# 3_waffling80_classyTKL-NMB_mcu.net
KiCad netlist of a schematic drawn in Altium Designer
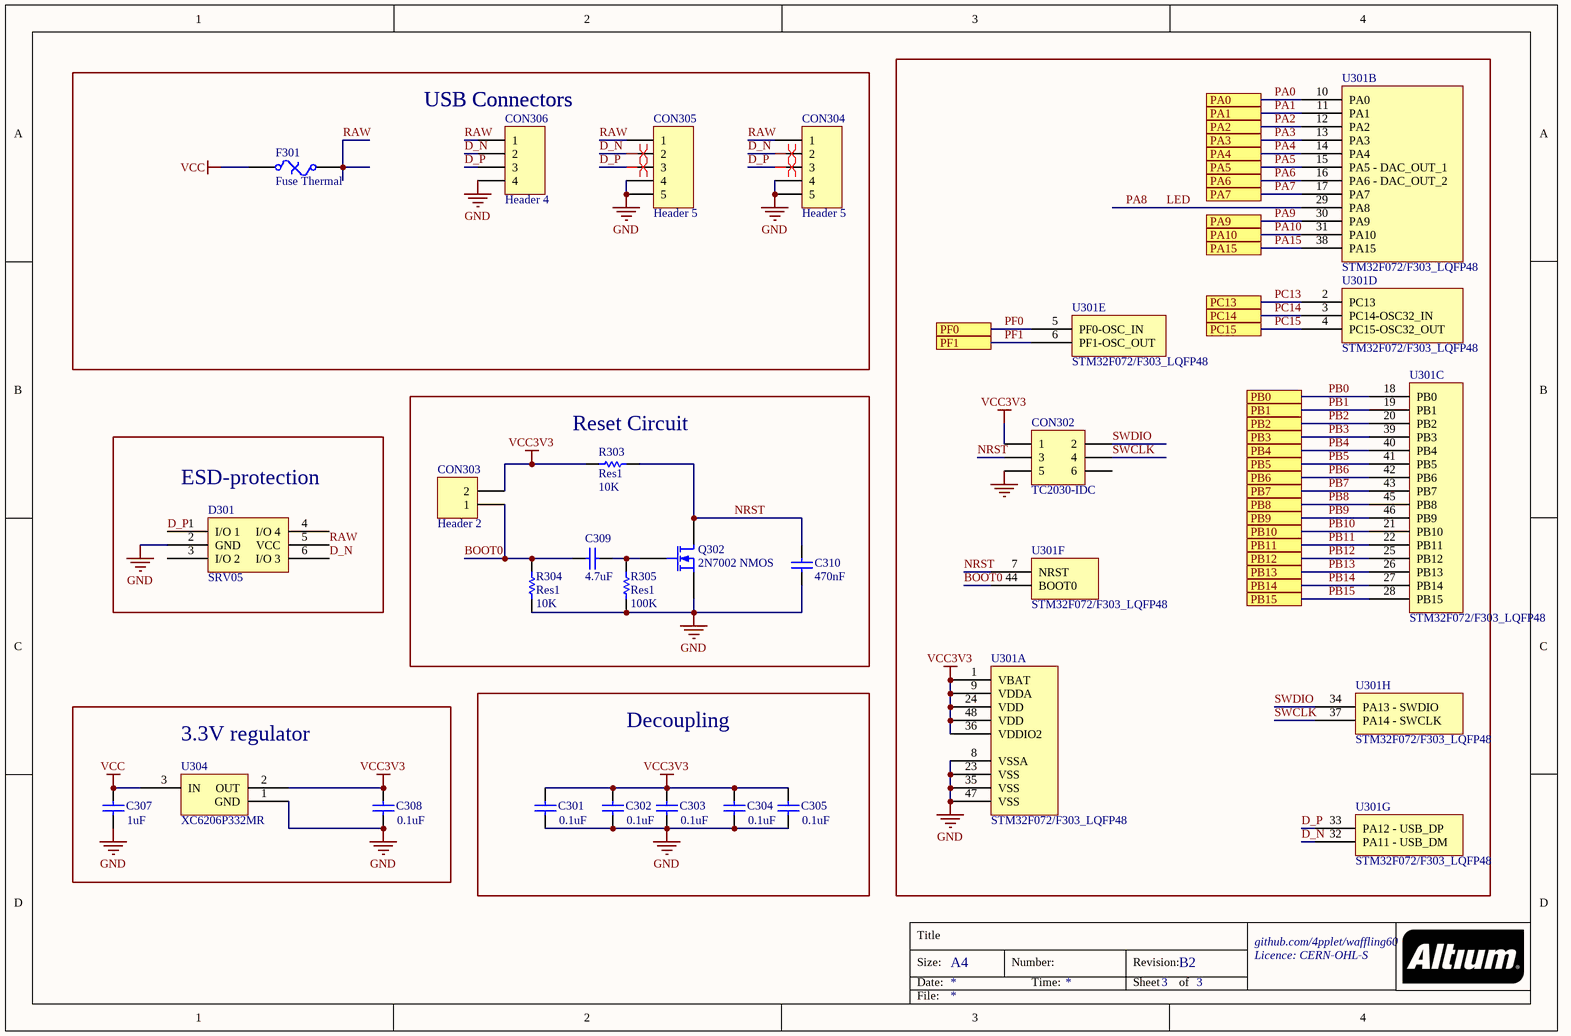
[diagram p0: 3_waffling80_classyTKL-NMB_mcu.SchDoc]

(export (version "E")
  (design (tool "Eeschema 10.0.6"))
  (components
    (comp (ref "C301")
      (value "0.1uF")
      (footprint "C0603[1608]")
      (description "Capacitor")
      (fields (field (name "LCSC PART #") "C14663") (field (name "MRF.PART") "CC0603KRX7R9BB104"))
      (libsource (lib "Miscellaneous Devices") (part "Cap"))
    )
    (comp (ref "C302")
      (value "0.1uF")
      (footprint "C0603[1608]")
      (description "Capacitor")
      (fields (field (name "LCSC PART #") "C14663") (field (name "MRF.PART") "CC0603KRX7R9BB104"))
      (libsource (lib "Miscellaneous Devices") (part "Cap"))
    )
    (comp (ref "C303")
      (value "0.1uF")
      (footprint "C0603[1608]")
      (description "Capacitor")
      (fields (field (name "LCSC PART #") "C14663") (field (name "MRF.PART") "CC0603KRX7R9BB104"))
      (libsource (lib "Miscellaneous Devices") (part "Cap"))
    )
    (comp (ref "C304")
      (value "0.1uF")
      (footprint "C0603[1608]")
      (description "Capacitor")
      (fields (field (name "LCSC PART #") "C14663") (field (name "MRF.PART") "CC0603KRX7R9BB104"))
      (libsource (lib "Miscellaneous Devices") (part "Cap"))
    )
    (comp (ref "C305")
      (value "0.1uF")
      (footprint "C0603[1608]")
      (description "Capacitor")
      (fields (field (name "LCSC PART #") "C14663") (field (name "MRF.PART") "CC0603KRX7R9BB104"))
      (libsource (lib "Miscellaneous Devices") (part "Cap"))
    )
    (comp (ref "C307")
      (value "1uF")
      (footprint "C0603[1608]")
      (description "Capacitor")
      (fields (field (name "LCSC PART #") "C15849") (field (name "MRF.PART") "CL10A105KB8NNNC"))
      (libsource (lib "Miscellaneous Devices") (part "Cap"))
    )
    (comp (ref "C308")
      (value "0.1uF")
      (footprint "C0603[1608]")
      (description "Capacitor")
      (fields (field (name "LCSC PART #") "C14663") (field (name "MRF.PART") "CC0603KRX7R9BB104"))
      (libsource (lib "Miscellaneous Devices") (part "Cap"))
    )
    (comp (ref "C309")
      (value "4.7uF")
      (footprint "C0603[1608]")
      (description "Capacitor")
      (fields (field (name "LCSC PART #") "C19666") (field (name "MRF.PART") "CL10A475KO8NNNC"))
      (libsource (lib "Miscellaneous Devices") (part "Cap"))
    )
    (comp (ref "C310")
      (value "470nF")
      (footprint "C0603[1608]")
      (description "Capacitor")
      (fields (field (name "LCSC PART #") "C1623") (field (name "MRF.PART") "CL10B474KA8NNNC"))
      (libsource (lib "Miscellaneous Devices") (part "Cap"))
    )
    (comp (ref "CON302")
      (value "TC2030-IDC")
      (footprint "TC2030-IDC-NL")
      (description "Header, 3-Pin, Dual row")
      (libsource (lib "Miscellaneous Connectors") (part "Header 3X2"))
    )
    (comp (ref "CON303")
      (value "Header 2")
      (footprint "HDR1X2")
      (description "Header, 2-Pin")
      (libsource (lib "Miscellaneous Connectors") (part "Header 2"))
    )
    (comp (ref "CON304")
      (value "Header 5")
      (footprint "UDB_COMBO_JST_MOLEX")
      (description "JST for USB daughter board")
      (fields (field (name "LCSC PART #") "C160404") (field (name "MRF.PART") "SM04B-SRSS-TB(LF)(SN)"))
      (libsource (lib "Miscellaneous Connectors") (part "Header 5"))
    )
    (comp (ref "CON305")
      (value "Header 5")
      (footprint "Molex 781710004")
      (description "JST for USB daughter board")
      (fields (field (name "LCSC PART #") "C588524") (field (name "MRF.PART") "781710004"))
      (libsource (lib "Miscellaneous Connectors") (part "Header 5"))
    )
    (comp (ref "CON306")
      (value "Header 4")
      (footprint "HDR1X4")
      (description "Header, 4-Pin")
      (libsource (lib "Miscellaneous Connectors") (part "Header 4"))
    )
    (comp (ref "D301")
      (value "SRV05")
      (footprint "SOT-23-6")
      (fields (field (name "LCSC PART #") "C85364") (field (name "MRF.PART") "SRV05-4-P-T7"))
      (libsource (lib "Keebs") (part "SRV05"))
    )
    (comp (ref "F301")
      (value "Fuse Thermal")
      (footprint "C1206[3216]")
      (description "Thermal Fuse")
      (fields (field (name "LCSC PART #") "C135338") (field (name "MRF.PART") "ASMD1206-050"))
      (libsource (lib "Miscellaneous Devices") (part "Fuse Thermal"))
    )
    (comp (ref "Q302")
      (value "2N7002 NMOS")
      (footprint "SOT-23-3")
      (description "N-Channel MOSFET")
      (fields (field (name "LCSC PART #") "C8545") (field (name "MRF.PART") "2N7002"))
      (libsource (lib "Miscellaneous Devices") (part "MOSFET-N"))
    )
    (comp (ref "R303")
      (value "Res1")
      (footprint "R0603[1608]")
      (description "Resistor")
      (fields
        (field (name "ALTIUM_VALUE") "10K")
        (field (name "LCSC PART #") "C25804")
        (field (name "MRF.PART") "0603WAF1002T5E")
      )
      (libsource (lib "Miscellaneous Devices") (part "Res1"))
    )
    (comp (ref "R304")
      (value "Res1")
      (footprint "R0603[1608]")
      (description "Resistor")
      (fields
        (field (name "ALTIUM_VALUE") "10K")
        (field (name "LCSC PART #") "C25804")
        (field (name "MRF.PART") "0603WAF1002T5E")
      )
      (libsource (lib "Miscellaneous Devices") (part "Res1"))
    )
    (comp (ref "R305")
      (value "Res1")
      (footprint "R0603[1608]")
      (description "Resistor")
      (fields
        (field (name "ALTIUM_VALUE") "100K")
        (field (name "LCSC PART #") "C25803")
        (field (name "MRF.PART") "0603WAF1003T5E")
      )
      (libsource (lib "Miscellaneous Devices") (part "Res1"))
    )
    (comp (ref "U301")
      (value "STM32F072/F303_LQFP48")
      (footprint "STM32 - COMBO 7X7MM")
      (fields (field (name "LCSC PART #") "C915660") (field (name "MRF.PART") "APM32F072CBT6"))
      (libsource (lib "Keebs") (part "STM32F072/F303_LQFP48"))
    )
    (comp (ref "U304")
      (value "XC6206P332MR")
      (footprint "SOT-23-3")
      (fields (field (name "LCSC PART #") "C5446"))
      (libsource (lib "Keebs") (part "SOT23 LDO"))
    )
  )
  (nets
    (net (code "1") (name "/BOOT0") (class "Default")
      (node (ref "C309") (pin "1") (pinfunction "1_1") (pintype "passive"))
      (node (ref "CON303") (pin "1") (pinfunction "1_1") (pintype "passive"))
      (node (ref "R304") (pin "1") (pinfunction "1_1") (pintype "passive"))
      (node (ref "U301") (pin "44") (pinfunction "BOOT0_44") (pintype "passive"))
    )
    (net (code "2") (name "/D_N") (class "Default")
      (node (ref "CON304") (pin "2") (pinfunction "2_2") (pintype "passive"))
      (node (ref "CON305") (pin "2") (pinfunction "2_2") (pintype "passive"))
      (node (ref "CON306") (pin "2") (pinfunction "2_2") (pintype "passive"))
      (node (ref "D301") (pin "6") (pinfunction "I/O_3_6") (pintype "passive"))
      (node (ref "U301") (pin "32") (pinfunction "PA11_-_USB_DM_32") (pintype "passive"))
    )
    (net (code "3") (name "/D_P") (class "Default")
      (node (ref "CON304") (pin "3") (pinfunction "3_3") (pintype "passive"))
      (node (ref "CON305") (pin "3") (pinfunction "3_3") (pintype "passive"))
      (node (ref "CON306") (pin "3") (pinfunction "3_3") (pintype "passive"))
      (node (ref "D301") (pin "1") (pinfunction "I/O_1_1") (pintype "passive"))
      (node (ref "U301") (pin "33") (pinfunction "PA12_-_USB_DP_33") (pintype "passive"))
    )
    (net (code "4") (name "/LED") (class "Default")
      (node (ref "U301") (pin "29") (pinfunction "PA8_29") (pintype "passive"))
    )
    (net (code "5") (name "/NRST") (class "Default")
      (node (ref "C310") (pin "1") (pinfunction "1_1") (pintype "passive"))
      (node (ref "CON302") (pin "3") (pinfunction "3_3") (pintype "passive"))
      (node (ref "Q302") (pin "3") (pinfunction "D_3") (pintype "passive"))
      (node (ref "R303") (pin "2") (pinfunction "2_2") (pintype "passive"))
      (node (ref "U301") (pin "7") (pinfunction "NRST_7") (pintype "passive"))
    )
    (net (code "6") (name "/PA0") (class "Default")
      (node (ref "U301") (pin "10") (pinfunction "PA0_10") (pintype "passive"))
    )
    (net (code "7") (name "/PA1") (class "Default")
      (node (ref "U301") (pin "11") (pinfunction "PA1_11") (pintype "passive"))
    )
    (net (code "8") (name "/PA2") (class "Default")
      (node (ref "U301") (pin "12") (pinfunction "PA2_12") (pintype "passive"))
    )
    (net (code "9") (name "/PA3") (class "Default")
      (node (ref "U301") (pin "13") (pinfunction "PA3_13") (pintype "passive"))
    )
    (net (code "10") (name "/PA4") (class "Default")
      (node (ref "U301") (pin "14") (pinfunction "PA4_14") (pintype "passive"))
    )
    (net (code "11") (name "/PA5") (class "Default")
      (node (ref "U301") (pin "15") (pinfunction "PA5_-_DAC_OUT_1_15") (pintype "passive"))
    )
    (net (code "12") (name "/PA6") (class "Default")
      (node (ref "U301") (pin "16") (pinfunction "PA6_-_DAC_OUT_2_16") (pintype "passive"))
    )
    (net (code "13") (name "/PA7") (class "Default")
      (node (ref "U301") (pin "17") (pinfunction "PA7_17") (pintype "passive"))
    )
    (net (code "14") (name "/PA9") (class "Default")
      (node (ref "U301") (pin "30") (pinfunction "PA9_30") (pintype "passive"))
    )
    (net (code "15") (name "/PA10") (class "Default")
      (node (ref "U301") (pin "31") (pinfunction "PA10_31") (pintype "passive"))
    )
    (net (code "16") (name "/PA15") (class "Default")
      (node (ref "U301") (pin "38") (pinfunction "PA15_38") (pintype "passive"))
    )
    (net (code "17") (name "/PB0") (class "Default")
      (node (ref "U301") (pin "18") (pinfunction "PB0_18") (pintype "passive"))
    )
    (net (code "18") (name "/PB1") (class "Default")
      (node (ref "U301") (pin "19") (pinfunction "PB1_19") (pintype "passive"))
    )
    (net (code "19") (name "/PB2") (class "Default")
      (node (ref "U301") (pin "20") (pinfunction "PB2_20") (pintype "passive"))
    )
    (net (code "20") (name "/PB3") (class "Default")
      (node (ref "U301") (pin "39") (pinfunction "PB3_39") (pintype "passive"))
    )
    (net (code "21") (name "/PB4") (class "Default")
      (node (ref "U301") (pin "40") (pinfunction "PB4_40") (pintype "passive"))
    )
    (net (code "22") (name "/PB5") (class "Default")
      (node (ref "U301") (pin "41") (pinfunction "PB5_41") (pintype "passive"))
    )
    (net (code "23") (name "/PB6") (class "Default")
      (node (ref "U301") (pin "42") (pinfunction "PB6_42") (pintype "passive"))
    )
    (net (code "24") (name "/PB7") (class "Default")
      (node (ref "U301") (pin "43") (pinfunction "PB7_43") (pintype "passive"))
    )
    (net (code "25") (name "/PB8") (class "Default")
      (node (ref "U301") (pin "45") (pinfunction "PB8_45") (pintype "passive"))
    )
    (net (code "26") (name "/PB9") (class "Default")
      (node (ref "U301") (pin "46") (pinfunction "PB9_46") (pintype "passive"))
    )
    (net (code "27") (name "/PB10") (class "Default")
      (node (ref "U301") (pin "21") (pinfunction "PB10_21") (pintype "passive"))
    )
    (net (code "28") (name "/PB11") (class "Default")
      (node (ref "U301") (pin "22") (pinfunction "PB11_22") (pintype "passive"))
    )
    (net (code "29") (name "/PB12") (class "Default")
      (node (ref "U301") (pin "25") (pinfunction "PB12_25") (pintype "passive"))
    )
    (net (code "30") (name "/PB13") (class "Default")
      (node (ref "U301") (pin "26") (pinfunction "PB13_26") (pintype "passive"))
    )
    (net (code "31") (name "/PB14") (class "Default")
      (node (ref "U301") (pin "27") (pinfunction "PB14_27") (pintype "passive"))
    )
    (net (code "32") (name "/PB15") (class "Default")
      (node (ref "U301") (pin "28") (pinfunction "PB15_28") (pintype "passive"))
    )
    (net (code "33") (name "/PC13") (class "Default")
      (node (ref "U301") (pin "2") (pinfunction "PC13_2") (pintype "passive"))
    )
    (net (code "34") (name "/PC14") (class "Default")
      (node (ref "U301") (pin "3") (pinfunction "PC14-OSC32_IN_3") (pintype "passive"))
    )
    (net (code "35") (name "/PC15") (class "Default")
      (node (ref "U301") (pin "4") (pinfunction "PC15-OSC32_OUT_4") (pintype "passive"))
    )
    (net (code "36") (name "/PF0") (class "Default")
      (node (ref "U301") (pin "5") (pinfunction "PF0-OSC_IN_5") (pintype "passive"))
    )
    (net (code "37") (name "/PF1") (class "Default")
      (node (ref "U301") (pin "6") (pinfunction "PF1-OSC_OUT_6") (pintype "passive"))
    )
    (net (code "38") (name "/RAW") (class "Default")
      (node (ref "CON304") (pin "1") (pinfunction "1_1") (pintype "passive"))
      (node (ref "CON305") (pin "1") (pinfunction "1_1") (pintype "passive"))
      (node (ref "CON306") (pin "1") (pinfunction "1_1") (pintype "passive"))
      (node (ref "D301") (pin "5") (pinfunction "VCC_5") (pintype "passive"))
      (node (ref "F301") (pin "2") (pinfunction "2_2") (pintype "passive"))
    )
    (net (code "39") (name "/SWCLK") (class "Default")
      (node (ref "CON302") (pin "4") (pinfunction "4_4") (pintype "passive"))
      (node (ref "U301") (pin "37") (pinfunction "PA14_-_SWCLK_37") (pintype "passive"))
    )
    (net (code "40") (name "/SWDIO") (class "Default")
      (node (ref "CON302") (pin "2") (pinfunction "2_2") (pintype "passive"))
      (node (ref "U301") (pin "34") (pinfunction "PA13_-_SWDIO_34") (pintype "passive"))
    )
    (net (code "41") (name "GND") (class "Default")
      (node (ref "C301") (pin "1") (pinfunction "1_1") (pintype "passive"))
      (node (ref "C302") (pin "1") (pinfunction "1_1") (pintype "passive"))
      (node (ref "C303") (pin "1") (pinfunction "1_1") (pintype "passive"))
      (node (ref "C304") (pin "1") (pinfunction "1_1") (pintype "passive"))
      (node (ref "C305") (pin "1") (pinfunction "1_1") (pintype "passive"))
      (node (ref "C307") (pin "1") (pinfunction "1_1") (pintype "passive"))
      (node (ref "C308") (pin "1") (pinfunction "1_1") (pintype "passive"))
      (node (ref "C310") (pin "2") (pinfunction "2_2") (pintype "passive"))
      (node (ref "CON302") (pin "5") (pinfunction "5_5") (pintype "passive"))
      (node (ref "CON304") (pin "4") (pinfunction "4_4") (pintype "passive"))
      (node (ref "CON304") (pin "5") (pinfunction "5_5") (pintype "passive"))
      (node (ref "CON305") (pin "4") (pinfunction "4_4") (pintype "passive"))
      (node (ref "CON305") (pin "5") (pinfunction "5_5") (pintype "passive"))
      (node (ref "CON306") (pin "4") (pinfunction "4_4") (pintype "passive"))
      (node (ref "D301") (pin "2") (pinfunction "GND_2") (pintype "passive"))
      (node (ref "Q302") (pin "2") (pinfunction "S_2") (pintype "passive"))
      (node (ref "R304") (pin "2") (pinfunction "2_2") (pintype "passive"))
      (node (ref "R305") (pin "2") (pinfunction "2_2") (pintype "passive"))
      (node (ref "U301") (pin "23") (pinfunction "VSS_23") (pintype "passive"))
      (node (ref "U301") (pin "35") (pinfunction "VSS_35") (pintype "passive"))
      (node (ref "U301") (pin "47") (pinfunction "VSS_47") (pintype "passive"))
      (node (ref "U301") (pin "8") (pinfunction "VSSA_8") (pintype "passive"))
      (node (ref "U304") (pin "1") (pinfunction "GND_1") (pintype "passive"))
    )
    (net (code "42") (name "Net-(Q302-G)") (class "Default")
      (node (ref "C309") (pin "2") (pinfunction "2_2") (pintype "passive"))
      (node (ref "Q302") (pin "1") (pinfunction "G_1") (pintype "passive"))
      (node (ref "R305") (pin "1") (pinfunction "1_1") (pintype "passive"))
    )
    (net (code "43") (name "VCC") (class "Default")
      (node (ref "C307") (pin "2") (pinfunction "2_2") (pintype "passive"))
      (node (ref "F301") (pin "1") (pinfunction "1_1") (pintype "passive"))
      (node (ref "U304") (pin "3") (pinfunction "IN_3") (pintype "passive"))
    )
    (net (code "44") (name "VCC3V3") (class "Default")
      (node (ref "C301") (pin "2") (pinfunction "2_2") (pintype "passive"))
      (node (ref "C302") (pin "2") (pinfunction "2_2") (pintype "passive"))
      (node (ref "C303") (pin "2") (pinfunction "2_2") (pintype "passive"))
      (node (ref "C304") (pin "2") (pinfunction "2_2") (pintype "passive"))
      (node (ref "C305") (pin "2") (pinfunction "2_2") (pintype "passive"))
      (node (ref "C308") (pin "2") (pinfunction "2_2") (pintype "passive"))
      (node (ref "CON302") (pin "1") (pinfunction "1_1") (pintype "passive"))
      (node (ref "CON303") (pin "2") (pinfunction "2_2") (pintype "passive"))
      (node (ref "R303") (pin "1") (pinfunction "1_1") (pintype "passive"))
      (node (ref "U301") (pin "1") (pinfunction "VBAT_1") (pintype "passive"))
      (node (ref "U301") (pin "24") (pinfunction "VDD_24") (pintype "passive"))
      (node (ref "U301") (pin "36") (pinfunction "VDDIO2_36") (pintype "passive"))
      (node (ref "U301") (pin "48") (pinfunction "VDD_48") (pintype "passive"))
      (node (ref "U301") (pin "9") (pinfunction "VDDA_9") (pintype "passive"))
      (node (ref "U304") (pin "2") (pinfunction "OUT_2") (pintype "passive"))
    )
    (net (code "45") (name "unconnected-(CON302-Pad6)") (class "Default")
      (node (ref "CON302") (pin "6") (pinfunction "6_6") (pintype "passive"))
    )
    (net (code "46") (name "unconnected-(D301-I{slash}O_2-Pad3)") (class "Default")
      (node (ref "D301") (pin "3") (pinfunction "I/O_2_3") (pintype "passive"))
    )
    (net (code "47") (name "unconnected-(D301-I{slash}O_4-Pad4)") (class "Default")
      (node (ref "D301") (pin "4") (pinfunction "I/O_4_4") (pintype "passive"))
    )
  )
)
